# Linefollower_Bluepill.net
KiCad netlist of a schematic drawn in EAGLE
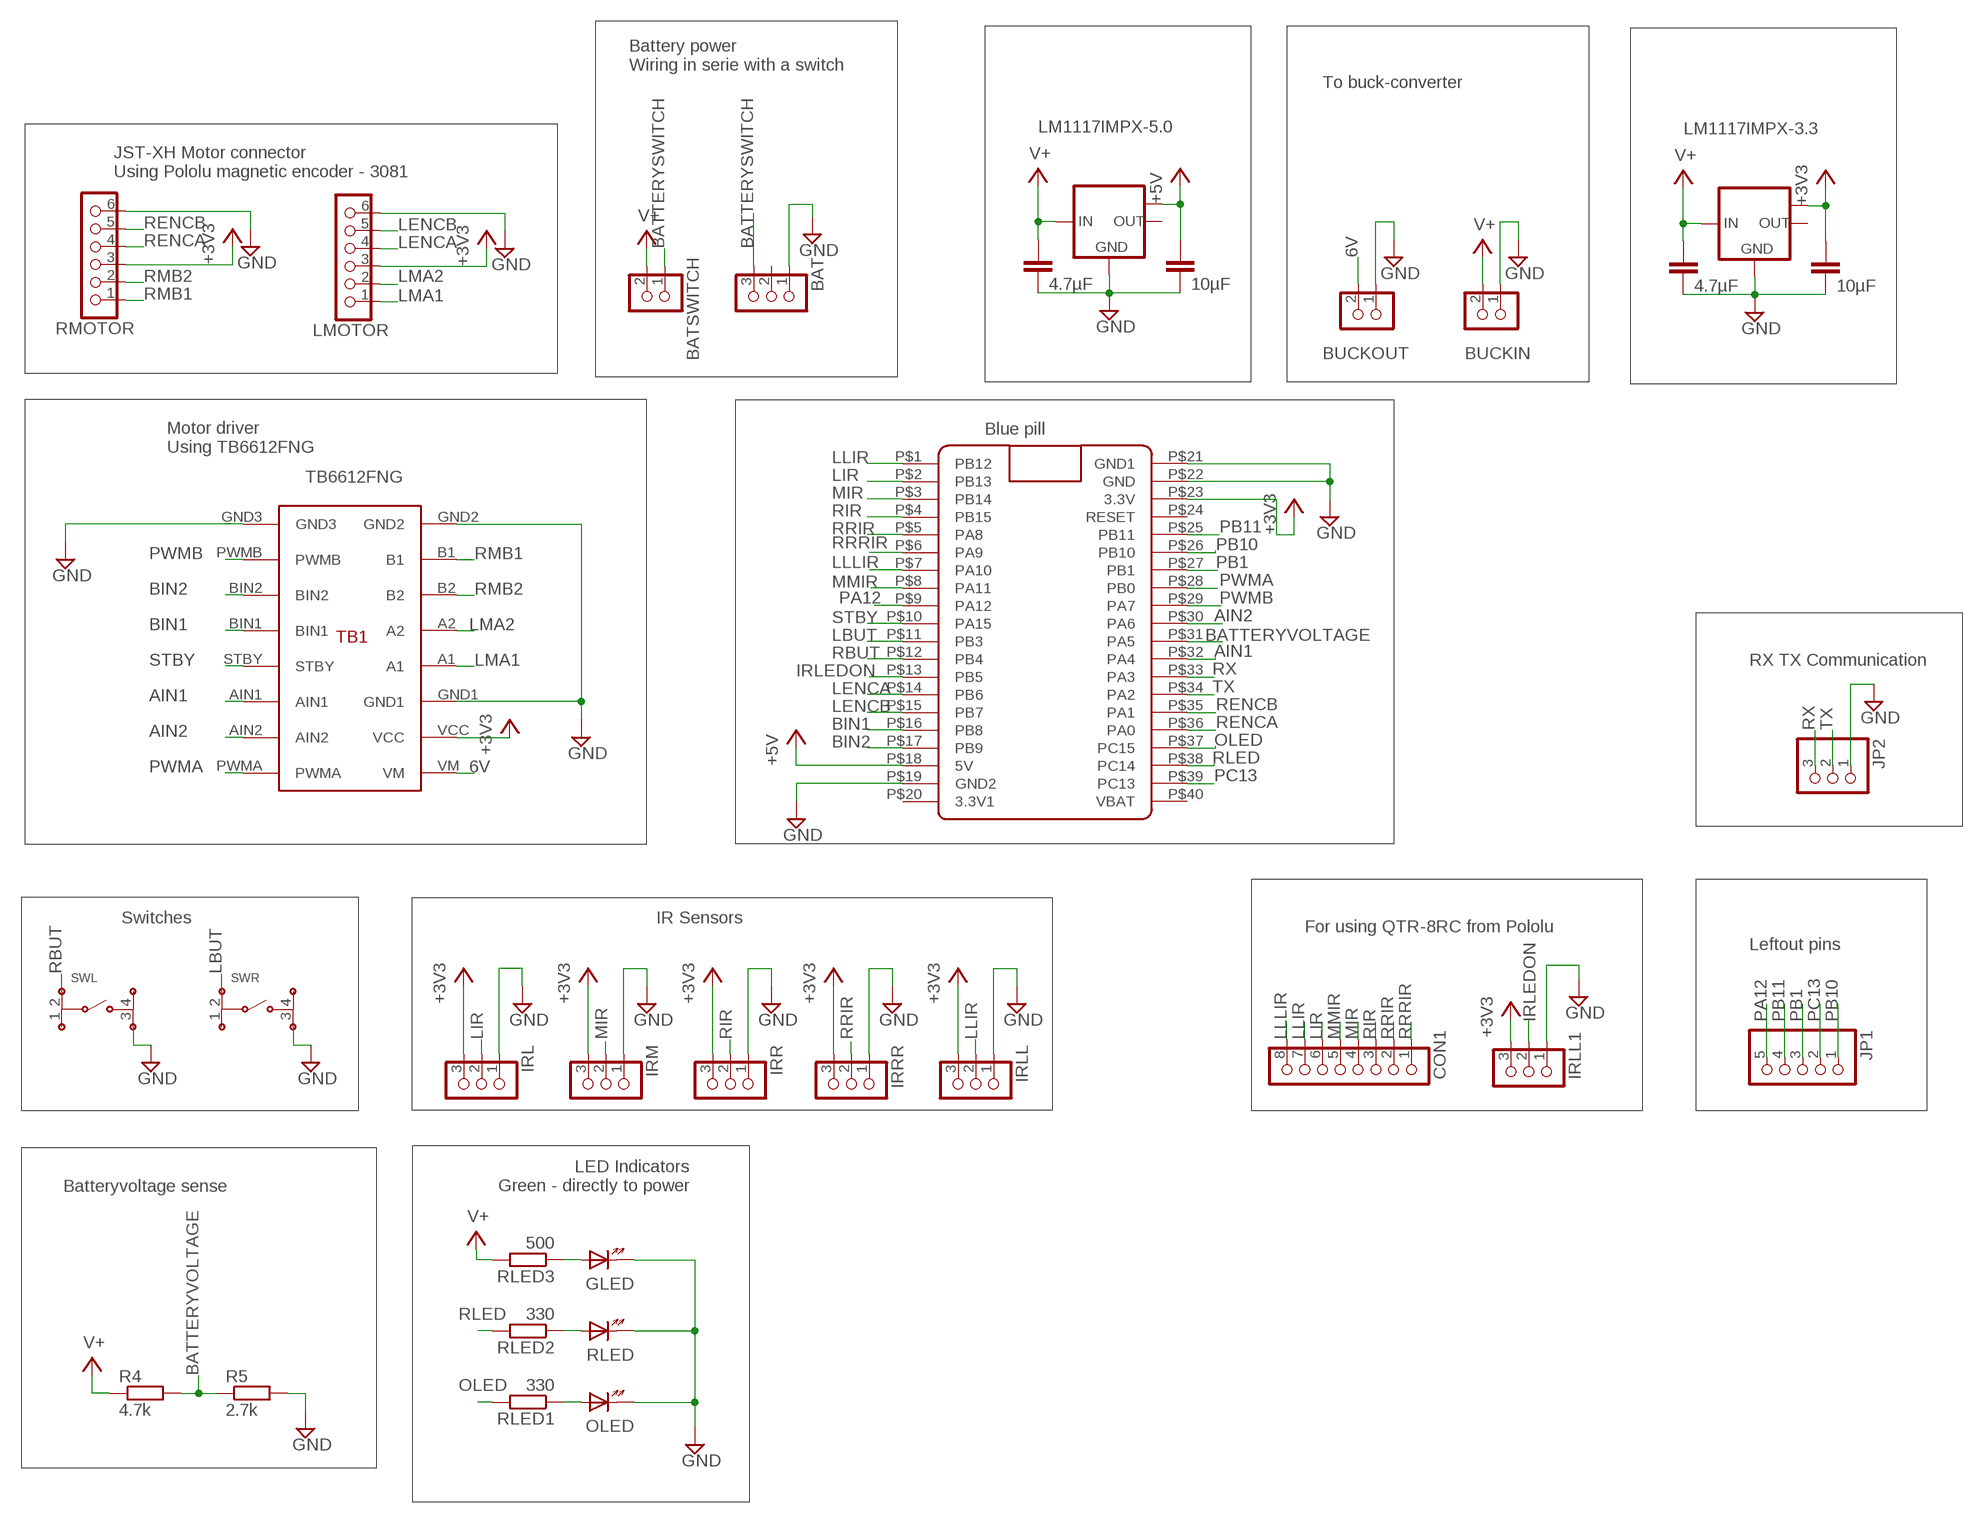
[diagram p0: schematic, sheet 1]

(export (version "E")
  (design (tool "Eeschema 10.0.6"))
  (components
    (comp (ref "BAT")
      (value "EH_B3B-EH")
      (footprint "eagle-import:B3B-EH")
      (libsource (lib "eagle-import") (part "EH_B3B-EH"))
    )
    (comp (ref "BATSWITCH")
      (value "EH_B2B-EH")
      (footprint "eagle-import:B2B-EH")
      (libsource (lib "eagle-import") (part "EH_B2B-EH"))
    )
    (comp (ref "BUCKIN")
      (value "EH_B2B-EH")
      (footprint "eagle-import:B2B-EH")
      (libsource (lib "eagle-import") (part "EH_B2B-EH"))
    )
    (comp (ref "BUCKOUT")
      (value "EH_B2B-EH")
      (footprint "eagle-import:B2B-EH")
      (libsource (lib "eagle-import") (part "EH_B2B-EH"))
    )
    (comp (ref "C1")
      (value "10µF")
      (footprint "eagle-import:C0805")
      (libsource (lib "eagle-import") (part "C0805"))
    )
    (comp (ref "C2")
      (value "4.7µF")
      (footprint "eagle-import:C0805")
      (libsource (lib "eagle-import") (part "C0805"))
    )
    (comp (ref "C3")
      (value "10µF")
      (footprint "eagle-import:C0805")
      (libsource (lib "eagle-import") (part "C0805"))
    )
    (comp (ref "C4")
      (value "4.7µF")
      (footprint "eagle-import:C0805")
      (libsource (lib "eagle-import") (part "C0805"))
    )
    (comp (ref "CON1")
      (value "EH_B8B-EH")
      (footprint "eagle-import:B8B-EH")
      (libsource (lib "eagle-import") (part "EH_B8B-EH"))
    )
    (comp (ref "GLED")
      (value "LED5MM")
      (footprint "eagle-import:LED5MM")
      (libsource (lib "eagle-import") (part "LED5MM"))
    )
    (comp (ref "IC1")
      (value "LM1117IMPX-5.0")
      (footprint "eagle-import:SOT223")
      (libsource (lib "eagle-import") (part "LM1117IMPX-5.0"))
    )
    (comp (ref "IC3")
      (value "LM1117IMPX-3.3")
      (footprint "eagle-import:SOT223")
      (libsource (lib "eagle-import") (part "LM1117IMPX-3.3"))
    )
    (comp (ref "IRL")
      (value "EH_B3B-EH")
      (footprint "eagle-import:B3B-EH")
      (libsource (lib "eagle-import") (part "EH_B3B-EH"))
    )
    (comp (ref "IRLL")
      (value "EH_B3B-EH")
      (footprint "eagle-import:B3B-EH")
      (libsource (lib "eagle-import") (part "EH_B3B-EH"))
    )
    (comp (ref "IRLL1")
      (value "EH_B3B-EH")
      (footprint "eagle-import:B3B-EH")
      (libsource (lib "eagle-import") (part "EH_B3B-EH"))
    )
    (comp (ref "IRM")
      (value "EH_B3B-EH")
      (footprint "eagle-import:B3B-EH")
      (libsource (lib "eagle-import") (part "EH_B3B-EH"))
    )
    (comp (ref "IRR")
      (value "EH_B3B-EH")
      (footprint "eagle-import:B3B-EH")
      (libsource (lib "eagle-import") (part "EH_B3B-EH"))
    )
    (comp (ref "IRRR")
      (value "EH_B3B-EH")
      (footprint "eagle-import:B3B-EH")
      (libsource (lib "eagle-import") (part "EH_B3B-EH"))
    )
    (comp (ref "JP1")
      (value "PINHD-1X5")
      (footprint "eagle-import:1X05")
      (libsource (lib "eagle-import") (part "PINHD-1X5"))
    )
    (comp (ref "JP2")
      (value "PINHD-1X3")
      (footprint "eagle-import:1X03")
      (libsource (lib "eagle-import") (part "PINHD-1X3"))
    )
    (comp (ref "LMOTOR")
      (value "EH_B6B-EH")
      (footprint "eagle-import:B6B-EH")
      (libsource (lib "eagle-import") (part "EH_B6B-EH"))
    )
    (comp (ref "OLED")
      (value "LED5MM")
      (footprint "eagle-import:LED5MM")
      (libsource (lib "eagle-import") (part "LED5MM"))
    )
    (comp (ref "R4")
      (value "4.7k")
      (footprint "eagle-import:R0603")
      (libsource (lib "eagle-import") (part "R0603"))
    )
    (comp (ref "R5")
      (value "2.7k")
      (footprint "eagle-import:R0603")
      (libsource (lib "eagle-import") (part "R0603"))
    )
    (comp (ref "RLED")
      (value "LED5MM")
      (footprint "eagle-import:LED5MM")
      (libsource (lib "eagle-import") (part "LED5MM"))
    )
    (comp (ref "RLED1")
      (value "330")
      (footprint "eagle-import:R0603")
      (libsource (lib "eagle-import") (part "R0603"))
    )
    (comp (ref "RLED2")
      (value "330")
      (footprint "eagle-import:R0603")
      (libsource (lib "eagle-import") (part "R0603"))
    )
    (comp (ref "RLED3")
      (value "500")
      (footprint "eagle-import:R0603")
      (libsource (lib "eagle-import") (part "R0603"))
    )
    (comp (ref "RMOTOR")
      (value "EH_B6B-EH")
      (footprint "eagle-import:B6B-EH")
      (libsource (lib "eagle-import") (part "EH_B6B-EH"))
    )
    (comp (ref "SWL")
      (value "SKHHA/D")
      (footprint "eagle-import:SKHHA_D")
      (libsource (lib "eagle-import") (part "SKHHA/D"))
    )
    (comp (ref "SWR")
      (value "SKHHA/D")
      (footprint "eagle-import:SKHHA_D")
      (libsource (lib "eagle-import") (part "SKHHA/D"))
    )
    (comp (ref "TB1")
      (value "TB6612FNG")
      (footprint "eagle-import:TB6612FNG")
      (libsource (lib "eagle-import") (part "TB6612FNG"))
    )
    (comp (ref "U$1")
      (value "BLUE_PILL")
      (footprint "eagle-import:BLUE_PILL")
      (libsource (lib "eagle-import") (part "BLUE_PILL"))
    )
  )
  (nets
    (net (code "1") (name "+3V3") (class "Default")
      (node (ref "C3") (pin "1") (pinfunction "1_1") (pintype "passive"))
      (node (ref "IC3") (pin "TAB") (pinfunction "OUT1_TAB") (pintype "passive"))
      (node (ref "IRL") (pin "3") (pinfunction "3_3") (pintype "passive"))
      (node (ref "IRLL") (pin "3") (pinfunction "3_3") (pintype "passive"))
      (node (ref "IRLL1") (pin "3") (pinfunction "3_3") (pintype "passive"))
      (node (ref "IRM") (pin "3") (pinfunction "3_3") (pintype "passive"))
      (node (ref "IRR") (pin "3") (pinfunction "3_3") (pintype "passive"))
      (node (ref "IRRR") (pin "3") (pinfunction "3_3") (pintype "passive"))
      (node (ref "LMOTOR") (pin "3") (pinfunction "3_3") (pintype "passive"))
      (node (ref "RMOTOR") (pin "3") (pinfunction "3_3") (pintype "passive"))
      (node (ref "TB1") (pin "VCC") (pinfunction "VCC_VCC") (pintype "bidirectional"))
      (node (ref "U$1") (pin "P$23") (pinfunction "3.3V_P$23") (pintype "bidirectional"))
    )
    (net (code "2") (name "+5V") (class "Default")
      (node (ref "C1") (pin "1") (pinfunction "1_1") (pintype "passive"))
      (node (ref "IC1") (pin "TAB") (pinfunction "OUT1_TAB") (pintype "passive"))
      (node (ref "U$1") (pin "P$18") (pinfunction "5V_P$18") (pintype "bidirectional"))
    )
    (net (code "3") (name "/6V") (class "Default")
      (node (ref "BUCKOUT") (pin "2") (pinfunction "2_2") (pintype "passive"))
      (node (ref "TB1") (pin "VM") (pinfunction "VM_VM") (pintype "bidirectional"))
    )
    (net (code "4") (name "/AIN1") (class "Default")
      (node (ref "TB1") (pin "AIN1") (pinfunction "AIN1_AIN1") (pintype "bidirectional"))
      (node (ref "U$1") (pin "P$32") (pinfunction "PA4_P$32") (pintype "bidirectional"))
    )
    (net (code "5") (name "/AIN2") (class "Default")
      (node (ref "TB1") (pin "AIN2") (pinfunction "AIN2_AIN2") (pintype "bidirectional"))
      (node (ref "U$1") (pin "P$30") (pinfunction "PA6_P$30") (pintype "bidirectional"))
    )
    (net (code "6") (name "/BATTERYSWITCH") (class "Default")
      (node (ref "BAT") (pin "3") (pinfunction "3_3") (pintype "passive"))
      (node (ref "BATSWITCH") (pin "1") (pinfunction "1_1") (pintype "passive"))
    )
    (net (code "7") (name "/BATTERYVOLTAGE") (class "Default")
      (node (ref "R4") (pin "2") (pinfunction "2_2") (pintype "passive"))
      (node (ref "R5") (pin "1") (pinfunction "1_1") (pintype "passive"))
      (node (ref "U$1") (pin "P$31") (pinfunction "PA5_P$31") (pintype "bidirectional"))
    )
    (net (code "8") (name "/BIN1") (class "Default")
      (node (ref "TB1") (pin "BIN1") (pinfunction "BIN1_BIN1") (pintype "bidirectional"))
      (node (ref "U$1") (pin "P$16") (pinfunction "PB8_P$16") (pintype "bidirectional"))
    )
    (net (code "9") (name "/BIN2") (class "Default")
      (node (ref "TB1") (pin "BIN2") (pinfunction "BIN2_BIN2") (pintype "bidirectional"))
      (node (ref "U$1") (pin "P$17") (pinfunction "PB9_P$17") (pintype "bidirectional"))
    )
    (net (code "10") (name "/IRLEDON") (class "Default")
      (node (ref "IRLL1") (pin "2") (pinfunction "2_2") (pintype "passive"))
      (node (ref "U$1") (pin "P$13") (pinfunction "PB5_P$13") (pintype "bidirectional"))
    )
    (net (code "11") (name "/LBUT") (class "Default")
      (node (ref "SWR") (pin "2") (pinfunction "2_2") (pintype "bidirectional"))
      (node (ref "U$1") (pin "P$11") (pinfunction "PB3_P$11") (pintype "bidirectional"))
    )
    (net (code "12") (name "/LENCA") (class "Default")
      (node (ref "LMOTOR") (pin "4") (pinfunction "4_4") (pintype "passive"))
      (node (ref "U$1") (pin "P$14") (pinfunction "PB6_P$14") (pintype "bidirectional"))
    )
    (net (code "13") (name "/LENCB") (class "Default")
      (node (ref "LMOTOR") (pin "5") (pinfunction "5_5") (pintype "passive"))
      (node (ref "U$1") (pin "P$15") (pinfunction "PB7_P$15") (pintype "bidirectional"))
    )
    (net (code "14") (name "/LIR") (class "Default")
      (node (ref "CON1") (pin "6") (pinfunction "6_6") (pintype "passive"))
      (node (ref "IRL") (pin "2") (pinfunction "2_2") (pintype "passive"))
      (node (ref "U$1") (pin "P$2") (pinfunction "PB13_P$2") (pintype "bidirectional"))
    )
    (net (code "15") (name "/LLIR") (class "Default")
      (node (ref "CON1") (pin "7") (pinfunction "7_7") (pintype "passive"))
      (node (ref "IRLL") (pin "2") (pinfunction "2_2") (pintype "passive"))
      (node (ref "U$1") (pin "P$1") (pinfunction "PB12_P$1") (pintype "bidirectional"))
    )
    (net (code "16") (name "/LLLIR") (class "Default")
      (node (ref "CON1") (pin "8") (pinfunction "8_8") (pintype "passive"))
      (node (ref "U$1") (pin "P$7") (pinfunction "PA10_P$7") (pintype "bidirectional"))
    )
    (net (code "17") (name "/LMA1") (class "Default")
      (node (ref "LMOTOR") (pin "1") (pinfunction "1_1") (pintype "passive"))
      (node (ref "TB1") (pin "A1") (pinfunction "A1_A1") (pintype "bidirectional"))
    )
    (net (code "18") (name "/LMA2") (class "Default")
      (node (ref "LMOTOR") (pin "2") (pinfunction "2_2") (pintype "passive"))
      (node (ref "TB1") (pin "A2") (pinfunction "A2_A2") (pintype "bidirectional"))
    )
    (net (code "19") (name "/MIR") (class "Default")
      (node (ref "CON1") (pin "4") (pinfunction "4_4") (pintype "passive"))
      (node (ref "IRM") (pin "2") (pinfunction "2_2") (pintype "passive"))
      (node (ref "U$1") (pin "P$3") (pinfunction "PB14_P$3") (pintype "bidirectional"))
    )
    (net (code "20") (name "/MMIR") (class "Default")
      (node (ref "CON1") (pin "5") (pinfunction "5_5") (pintype "passive"))
      (node (ref "U$1") (pin "P$8") (pinfunction "PA11_P$8") (pintype "bidirectional"))
    )
    (net (code "21") (name "/OLED") (class "Default")
      (node (ref "RLED1") (pin "2") (pinfunction "2_2") (pintype "passive"))
      (node (ref "U$1") (pin "P$37") (pinfunction "PC15_P$37") (pintype "bidirectional"))
    )
    (net (code "22") (name "/PA12") (class "Default")
      (node (ref "JP1") (pin "5") (pinfunction "5_5") (pintype "passive"))
      (node (ref "U$1") (pin "P$9") (pinfunction "PA12_P$9") (pintype "bidirectional"))
    )
    (net (code "23") (name "/PB1") (class "Default")
      (node (ref "JP1") (pin "3") (pinfunction "3_3") (pintype "passive"))
      (node (ref "U$1") (pin "P$27") (pinfunction "PB1_P$27") (pintype "bidirectional"))
    )
    (net (code "24") (name "/PB10") (class "Default")
      (node (ref "JP1") (pin "1") (pinfunction "1_1") (pintype "passive"))
      (node (ref "U$1") (pin "P$26") (pinfunction "PB10_P$26") (pintype "bidirectional"))
    )
    (net (code "25") (name "/PB11") (class "Default")
      (node (ref "JP1") (pin "4") (pinfunction "4_4") (pintype "passive"))
      (node (ref "U$1") (pin "P$25") (pinfunction "PB11_P$25") (pintype "bidirectional"))
    )
    (net (code "26") (name "/PC13") (class "Default")
      (node (ref "JP1") (pin "2") (pinfunction "2_2") (pintype "passive"))
      (node (ref "U$1") (pin "P$39") (pinfunction "PC13_P$39") (pintype "bidirectional"))
    )
    (net (code "27") (name "/PWMA") (class "Default")
      (node (ref "TB1") (pin "PWMA") (pinfunction "PWMA_PWMA") (pintype "bidirectional"))
      (node (ref "U$1") (pin "P$28") (pinfunction "PB0_P$28") (pintype "bidirectional"))
    )
    (net (code "28") (name "/PWMB") (class "Default")
      (node (ref "TB1") (pin "PWMB") (pinfunction "PWMB_PWMB") (pintype "bidirectional"))
      (node (ref "U$1") (pin "P$29") (pinfunction "PA7_P$29") (pintype "bidirectional"))
    )
    (net (code "29") (name "/RBUT") (class "Default")
      (node (ref "SWL") (pin "2") (pinfunction "2_2") (pintype "bidirectional"))
      (node (ref "U$1") (pin "P$12") (pinfunction "PB4_P$12") (pintype "bidirectional"))
    )
    (net (code "30") (name "/RENCA") (class "Default")
      (node (ref "RMOTOR") (pin "4") (pinfunction "4_4") (pintype "passive"))
      (node (ref "U$1") (pin "P$36") (pinfunction "PA0_P$36") (pintype "bidirectional"))
    )
    (net (code "31") (name "/RENCB") (class "Default")
      (node (ref "RMOTOR") (pin "5") (pinfunction "5_5") (pintype "passive"))
      (node (ref "U$1") (pin "P$35") (pinfunction "PA1_P$35") (pintype "bidirectional"))
    )
    (net (code "32") (name "/RIR") (class "Default")
      (node (ref "CON1") (pin "3") (pinfunction "3_3") (pintype "passive"))
      (node (ref "IRR") (pin "2") (pinfunction "2_2") (pintype "passive"))
      (node (ref "U$1") (pin "P$4") (pinfunction "PB15_P$4") (pintype "bidirectional"))
    )
    (net (code "33") (name "/RLED") (class "Default")
      (node (ref "RLED2") (pin "2") (pinfunction "2_2") (pintype "passive"))
      (node (ref "U$1") (pin "P$38") (pinfunction "PC14_P$38") (pintype "bidirectional"))
    )
    (net (code "34") (name "/RMB1") (class "Default")
      (node (ref "RMOTOR") (pin "1") (pinfunction "1_1") (pintype "passive"))
      (node (ref "TB1") (pin "B1") (pinfunction "B1_B1") (pintype "bidirectional"))
    )
    (net (code "35") (name "/RMB2") (class "Default")
      (node (ref "RMOTOR") (pin "2") (pinfunction "2_2") (pintype "passive"))
      (node (ref "TB1") (pin "B2") (pinfunction "B2_B2") (pintype "bidirectional"))
    )
    (net (code "36") (name "/RRIR") (class "Default")
      (node (ref "CON1") (pin "2") (pinfunction "2_2") (pintype "passive"))
      (node (ref "IRRR") (pin "2") (pinfunction "2_2") (pintype "passive"))
      (node (ref "U$1") (pin "P$5") (pinfunction "PA8_P$5") (pintype "bidirectional"))
    )
    (net (code "37") (name "/RRRIR") (class "Default")
      (node (ref "CON1") (pin "1") (pinfunction "1_1") (pintype "passive"))
      (node (ref "U$1") (pin "P$6") (pinfunction "PA9_P$6") (pintype "bidirectional"))
    )
    (net (code "38") (name "/RX") (class "Default")
      (node (ref "JP2") (pin "3") (pinfunction "3_3") (pintype "passive"))
      (node (ref "U$1") (pin "P$33") (pinfunction "PA3_P$33") (pintype "bidirectional"))
    )
    (net (code "39") (name "/STBY") (class "Default")
      (node (ref "TB1") (pin "STBY") (pinfunction "STBY_STBY") (pintype "bidirectional"))
      (node (ref "U$1") (pin "P$10") (pinfunction "PA15_P$10") (pintype "bidirectional"))
    )
    (net (code "40") (name "/TX") (class "Default")
      (node (ref "JP2") (pin "2") (pinfunction "2_2") (pintype "passive"))
      (node (ref "U$1") (pin "P$34") (pinfunction "PA2_P$34") (pintype "bidirectional"))
    )
    (net (code "41") (name "GND") (class "Default")
      (node (ref "BAT") (pin "1") (pinfunction "1_1") (pintype "passive"))
      (node (ref "BUCKIN") (pin "1") (pinfunction "1_1") (pintype "passive"))
      (node (ref "BUCKOUT") (pin "1") (pinfunction "1_1") (pintype "passive"))
      (node (ref "C1") (pin "2") (pinfunction "2_2") (pintype "passive"))
      (node (ref "C2") (pin "2") (pinfunction "2_2") (pintype "passive"))
      (node (ref "C3") (pin "2") (pinfunction "2_2") (pintype "passive"))
      (node (ref "C4") (pin "2") (pinfunction "2_2") (pintype "passive"))
      (node (ref "GLED") (pin "K") (pinfunction "K_K") (pintype "passive"))
      (node (ref "IC1") (pin "1") (pinfunction "GND_1") (pintype "input"))
      (node (ref "IC3") (pin "1") (pinfunction "GND_1") (pintype "input"))
      (node (ref "IRL") (pin "1") (pinfunction "1_1") (pintype "passive"))
      (node (ref "IRLL") (pin "1") (pinfunction "1_1") (pintype "passive"))
      (node (ref "IRLL1") (pin "1") (pinfunction "1_1") (pintype "passive"))
      (node (ref "IRM") (pin "1") (pinfunction "1_1") (pintype "passive"))
      (node (ref "IRR") (pin "1") (pinfunction "1_1") (pintype "passive"))
      (node (ref "IRRR") (pin "1") (pinfunction "1_1") (pintype "passive"))
      (node (ref "JP2") (pin "1") (pinfunction "1_1") (pintype "passive"))
      (node (ref "LMOTOR") (pin "6") (pinfunction "6_6") (pintype "passive"))
      (node (ref "OLED") (pin "K") (pinfunction "K_K") (pintype "passive"))
      (node (ref "R5") (pin "2") (pinfunction "2_2") (pintype "passive"))
      (node (ref "RLED") (pin "K") (pinfunction "K_K") (pintype "passive"))
      (node (ref "RMOTOR") (pin "6") (pinfunction "6_6") (pintype "passive"))
      (node (ref "SWL") (pin "3") (pinfunction "3_3") (pintype "bidirectional"))
      (node (ref "SWR") (pin "3") (pinfunction "3_3") (pintype "bidirectional"))
      (node (ref "TB1") (pin "GND1") (pinfunction "GND1_GND1") (pintype "bidirectional"))
      (node (ref "TB1") (pin "GND2") (pinfunction "GND2_GND2") (pintype "bidirectional"))
      (node (ref "TB1") (pin "GND3") (pinfunction "GND3_GND3") (pintype "bidirectional"))
      (node (ref "U$1") (pin "P$19") (pinfunction "GND2_P$19") (pintype "bidirectional"))
      (node (ref "U$1") (pin "P$21") (pinfunction "GND1_P$21") (pintype "power_in"))
      (node (ref "U$1") (pin "P$22") (pinfunction "GND_P$22") (pintype "bidirectional"))
    )
    (net (code "42") (name "Net-(GLED-PadA)") (class "Default")
      (node (ref "GLED") (pin "A") (pinfunction "A_A") (pintype "passive"))
      (node (ref "RLED3") (pin "1") (pinfunction "1_1") (pintype "passive"))
    )
    (net (code "43") (name "Net-(OLED-PadA)") (class "Default")
      (node (ref "OLED") (pin "A") (pinfunction "A_A") (pintype "passive"))
      (node (ref "RLED1") (pin "1") (pinfunction "1_1") (pintype "passive"))
    )
    (net (code "44") (name "Net-(RLED-PadA)") (class "Default")
      (node (ref "RLED") (pin "A") (pinfunction "A_A") (pintype "passive"))
      (node (ref "RLED2") (pin "1") (pinfunction "1_1") (pintype "passive"))
    )
    (net (code "45") (name "V+") (class "Default")
      (node (ref "BATSWITCH") (pin "2") (pinfunction "2_2") (pintype "passive"))
      (node (ref "BUCKIN") (pin "2") (pinfunction "2_2") (pintype "passive"))
      (node (ref "C2") (pin "1") (pinfunction "1_1") (pintype "passive"))
      (node (ref "C4") (pin "1") (pinfunction "1_1") (pintype "passive"))
      (node (ref "IC1") (pin "3") (pinfunction "IN_3") (pintype "input"))
      (node (ref "IC3") (pin "3") (pinfunction "IN_3") (pintype "input"))
      (node (ref "R4") (pin "1") (pinfunction "1_1") (pintype "passive"))
      (node (ref "RLED3") (pin "2") (pinfunction "2_2") (pintype "passive"))
    )
    (net (code "46") (name "unconnected-(BAT-Pad2)") (class "Default")
      (node (ref "BAT") (pin "2") (pinfunction "2_2") (pintype "passive"))
    )
    (net (code "47") (name "unconnected-(IC1-OUT-Pad2)") (class "Default")
      (node (ref "IC1") (pin "2") (pinfunction "OUT_2") (pintype "passive"))
    )
    (net (code "48") (name "unconnected-(IC3-OUT-Pad2)") (class "Default")
      (node (ref "IC3") (pin "2") (pinfunction "OUT_2") (pintype "passive"))
    )
    (net (code "49") (name "unconnected-(SWL-Pad1)") (class "Default")
      (node (ref "SWL") (pin "1") (pinfunction "1_1") (pintype "bidirectional"))
    )
    (net (code "50") (name "unconnected-(SWL-Pad4)") (class "Default")
      (node (ref "SWL") (pin "4") (pinfunction "4_4") (pintype "bidirectional"))
    )
    (net (code "51") (name "unconnected-(SWR-Pad1)") (class "Default")
      (node (ref "SWR") (pin "1") (pinfunction "1_1") (pintype "bidirectional"))
    )
    (net (code "52") (name "unconnected-(SWR-Pad4)") (class "Default")
      (node (ref "SWR") (pin "4") (pinfunction "4_4") (pintype "bidirectional"))
    )
    (net (code "53") (name "unconnected-(U$1-3.3V1-PadP$20)") (class "Default")
      (node (ref "U$1") (pin "P$20") (pinfunction "3.3V1_P$20") (pintype "bidirectional"))
    )
    (net (code "54") (name "unconnected-(U$1-RESET-PadP$24)") (class "Default")
      (node (ref "U$1") (pin "P$24") (pinfunction "RESET_P$24") (pintype "bidirectional"))
    )
    (net (code "55") (name "unconnected-(U$1-VBAT-PadP$40)") (class "Default")
      (node (ref "U$1") (pin "P$40") (pinfunction "VBAT_P$40") (pintype "bidirectional"))
    )
  )
)
